# simple-power-monitor.net
KiCad netlist of a schematic drawn in EAGLE
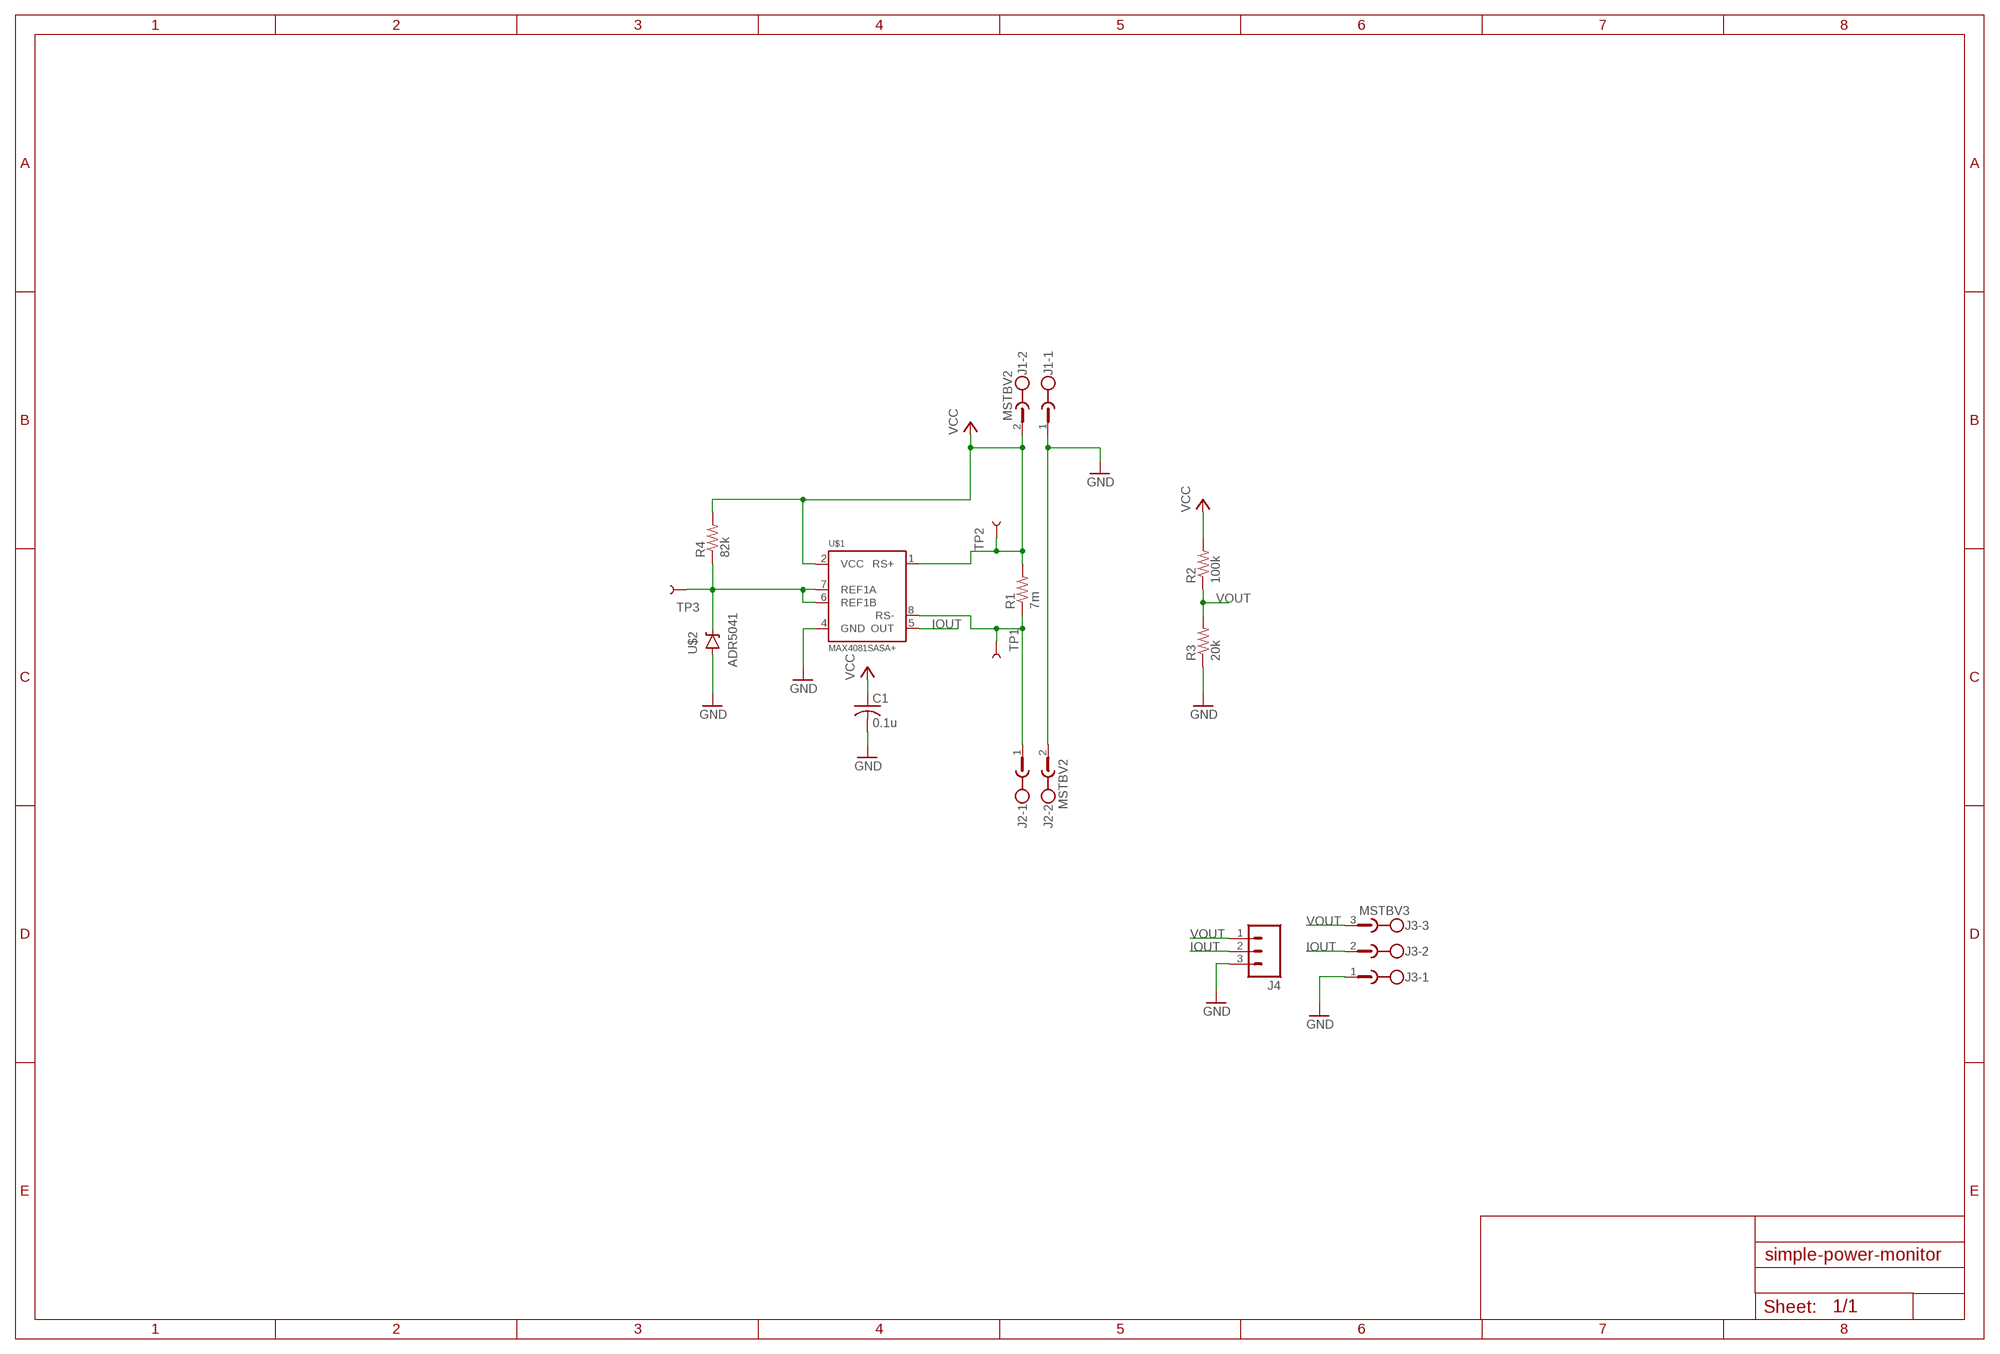
[diagram p0: schematic, sheet 1]

(export (version "E")
  (design (tool "Eeschema 10.0.6"))
  (components
    (comp (ref "C1")
      (value "0.1u")
      (footprint "eagle-import:C0805K")
      (libsource (lib "eagle-import") (part "C-USC0805K"))
    )
    (comp (ref "J1")
      (value "MSTBV2")
      (footprint "eagle-import:MSTBV2")
      (fields (field (name "MPN") "MSTBV 2,5/2-GF-5.08"))
      (libsource (lib "eagle-import") (part "MSTBV2"))
    )
    (comp (ref "J2")
      (value "MSTBV2")
      (footprint "eagle-import:MSTBV2")
      (fields (field (name "MPN") "MSTBV 2,5/2-GF-5.08"))
      (libsource (lib "eagle-import") (part "MSTBV2"))
    )
    (comp (ref "J3")
      (value "MSTBV3")
      (footprint "eagle-import:MSTBV3")
      (fields (field (name "MPN") "MSTBV 2,5/3-GF-5.08"))
      (libsource (lib "eagle-import") (part "MSTBV3"))
    )
    (comp (ref "J4")
      (value "M03PTH")
      (footprint "eagle-import:1X03")
      (libsource (lib "eagle-import") (part "M03PTH"))
    )
    (comp (ref "R1")
      (value "7m")
      (footprint "eagle-import:R2010")
      (libsource (lib "eagle-import") (part "R-US_R2010"))
    )
    (comp (ref "R2")
      (value "100k")
      (footprint "eagle-import:R0805")
      (libsource (lib "eagle-import") (part "R-US_R0805"))
    )
    (comp (ref "R3")
      (value "20k")
      (footprint "eagle-import:R0805")
      (libsource (lib "eagle-import") (part "R-US_R0805"))
    )
    (comp (ref "R4")
      (value "82k")
      (footprint "eagle-import:R0805")
      (libsource (lib "eagle-import") (part "R-US_R0805"))
    )
    (comp (ref "TP1")
      (value "TEST-POINTTP_15TH_THRU")
      (footprint "eagle-import:TP_15TH")
      (libsource (lib "eagle-import") (part "TEST-POINTTP_15TH_THRU"))
    )
    (comp (ref "TP2")
      (value "TEST-POINTTP_15TH_THRU")
      (footprint "eagle-import:TP_15TH")
      (libsource (lib "eagle-import") (part "TEST-POINTTP_15TH_THRU"))
    )
    (comp (ref "TP3")
      (value "TEST-POINTTP_15TH_THRU")
      (footprint "eagle-import:TP_15TH")
      (libsource (lib "eagle-import") (part "TEST-POINTTP_15TH_THRU"))
    )
    (comp (ref "U$1")
      (value "MAX4081SASA+")
      (footprint "eagle-import:SO8")
      (libsource (lib "eagle-import") (part "MAX4081SASA+"))
    )
    (comp (ref "U$2")
      (value "ADR5041")
      (footprint "eagle-import:SOT23-3")
      (libsource (lib "eagle-import") (part "ADR5041"))
    )
  )
  (nets
    (net (code "1") (name "/IOUT") (class "Default")
      (node (ref "J3") (pin "2") (pinfunction "1_2") (pintype "passive"))
      (node (ref "J4") (pin "2") (pinfunction "2_2") (pintype "passive"))
      (node (ref "U$1") (pin "5") (pinfunction "OUT_5") (pintype "bidirectional"))
    )
    (net (code "2") (name "/VOUT") (class "Default")
      (node (ref "J3") (pin "3") (pinfunction "1_3") (pintype "passive"))
      (node (ref "J4") (pin "1") (pinfunction "1_1") (pintype "passive"))
      (node (ref "R2") (pin "1") (pinfunction "1_1") (pintype "passive"))
      (node (ref "R3") (pin "2") (pinfunction "2_2") (pintype "passive"))
    )
    (net (code "3") (name "GND") (class "Default")
      (node (ref "C1") (pin "2") (pinfunction "2_2") (pintype "passive"))
      (node (ref "J1") (pin "1") (pinfunction "1_1") (pintype "passive"))
      (node (ref "J2") (pin "2") (pinfunction "1_2") (pintype "passive"))
      (node (ref "J3") (pin "1") (pinfunction "1_1") (pintype "passive"))
      (node (ref "J4") (pin "3") (pinfunction "3_3") (pintype "passive"))
      (node (ref "R3") (pin "1") (pinfunction "1_1") (pintype "passive"))
      (node (ref "U$1") (pin "4") (pinfunction "GND_4") (pintype "bidirectional"))
      (node (ref "U$2") (pin "2") (pinfunction "A_2") (pintype "passive"))
    )
    (net (code "4") (name "Net-(TP1-1)") (class "Default")
      (node (ref "J2") (pin "1") (pinfunction "1_1") (pintype "passive"))
      (node (ref "R1") (pin "1") (pinfunction "1_1") (pintype "passive"))
      (node (ref "TP1") (pin "P$1") (pinfunction "1_P$1") (pintype "bidirectional"))
      (node (ref "U$1") (pin "8") (pinfunction "RS-_8") (pintype "bidirectional"))
    )
    (net (code "5") (name "Net-(TP3-1)") (class "Default")
      (node (ref "R4") (pin "1") (pinfunction "1_1") (pintype "passive"))
      (node (ref "TP3") (pin "P$1") (pinfunction "1_P$1") (pintype "bidirectional"))
      (node (ref "U$1") (pin "6") (pinfunction "REF1B_6") (pintype "bidirectional"))
      (node (ref "U$1") (pin "7") (pinfunction "REF1A_7") (pintype "bidirectional"))
      (node (ref "U$2") (pin "1") (pinfunction "C_1") (pintype "passive"))
    )
    (net (code "6") (name "VCC") (class "Default")
      (node (ref "C1") (pin "1") (pinfunction "1_1") (pintype "passive"))
      (node (ref "J1") (pin "2") (pinfunction "1_2") (pintype "passive"))
      (node (ref "R1") (pin "2") (pinfunction "2_2") (pintype "passive"))
      (node (ref "R2") (pin "2") (pinfunction "2_2") (pintype "passive"))
      (node (ref "R4") (pin "2") (pinfunction "2_2") (pintype "passive"))
      (node (ref "TP2") (pin "P$1") (pinfunction "1_P$1") (pintype "bidirectional"))
      (node (ref "U$1") (pin "1") (pinfunction "RS+_1") (pintype "bidirectional"))
      (node (ref "U$1") (pin "2") (pinfunction "VCC_2") (pintype "bidirectional"))
    )
  )
)
